# JoystickButtons.net
KiCad netlist of a schematic drawn in Altium Designer
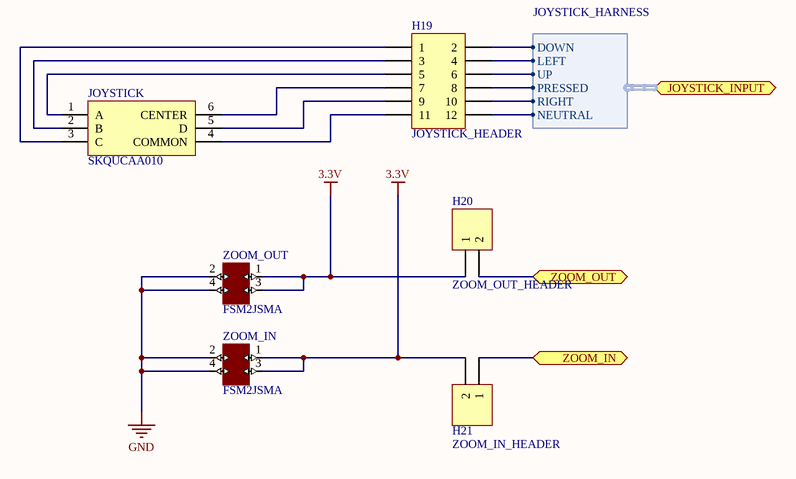
[diagram p0: JoystickButtons.SchDoc]

(export (version "E")
  (design (tool "Eeschema 10.0.6"))
  (components
    (comp (ref "H19")
      (value "JOYSTICK_HEADER")
      (footprint "HDR2X6")
      (description "Header, 6-Pin, Dual row")
      (fields (field (name "PUBLISHER") "Altium Limited"))
      (libsource (lib "Miscellaneous Connectors") (part "Header 6X2"))
    )
    (comp (ref "H20")
      (value "ZOOM_OUT_HEADER")
      (footprint "HDR1X2")
      (description "Header, 2-Pin")
      (fields (field (name "PUBLISHER") "Altium Limited"))
      (libsource (lib "") (part "Header 2_1"))
    )
    (comp (ref "H21")
      (value "ZOOM_IN_HEADER")
      (footprint "HDR1X2")
      (description "Header, 2-Pin")
      (fields (field (name "PUBLISHER") "Altium Limited"))
      (libsource (lib "Miscellaneous Connectors") (part "Header 2"))
    )
    (comp (ref "JOYSTICK")
      (value "SKQUCAA010")
      (footprint "5-WAY-JOYSTICK")
      (libsource (lib "Vector Library") (part "SKQUCAA010"))
    )
    (comp (ref "ZOOM_IN")
      (value "FSM2JSMA")
      (footprint "Button")
      (libsource (lib "Vector Library") (part "switch-button"))
    )
    (comp (ref "ZOOM_OUT")
      (value "FSM2JSMA")
      (footprint "Button")
      (libsource (lib "Vector Library") (part "switch-button"))
    )
  )
  (nets
    (net (code "2") (name "/DOWN") (class "Default")
      (node (ref "H19") (pin "2") (pinfunction "2_2") (pintype "passive"))
    )
    (net (code "3") (name "/LEFT") (class "Default")
      (node (ref "H19") (pin "4") (pinfunction "4_4") (pintype "passive"))
    )
    (net (code "4") (name "/NEUTRAL") (class "Default")
      (node (ref "H19") (pin "12") (pinfunction "12_12") (pintype "passive"))
    )
    (net (code "5") (name "/PRESSED") (class "Default")
      (node (ref "H19") (pin "8") (pinfunction "8_8") (pintype "passive"))
    )
    (net (code "6") (name "/RIGHT") (class "Default")
      (node (ref "H19") (pin "10") (pinfunction "10_10") (pintype "passive"))
    )
    (net (code "7") (name "/UP") (class "Default")
      (node (ref "H19") (pin "6") (pinfunction "6_6") (pintype "passive"))
    )
    (net (code "8") (name "/ZOOM_IN") (class "Default")
      (node (ref "H21") (pin "1") (pinfunction "1_1") (pintype "passive"))
    )
    (net (code "9") (name "/ZOOM_OUT") (class "Default")
      (node (ref "H20") (pin "2") (pinfunction "2_2") (pintype "passive"))
    )
    (net (code "11") (name "3.3V") (class "Default")
      (node (ref "H20") (pin "1") (pinfunction "1_1") (pintype "passive"))
      (node (ref "H21") (pin "2") (pinfunction "2_2") (pintype "passive"))
      (node (ref "ZOOM_IN") (pin "1") (pinfunction "1_1") (pintype "bidirectional"))
      (node (ref "ZOOM_IN") (pin "3") (pinfunction "3_3") (pintype "bidirectional"))
      (node (ref "ZOOM_OUT") (pin "1") (pinfunction "1_1") (pintype "bidirectional"))
      (node (ref "ZOOM_OUT") (pin "3") (pinfunction "3_3") (pintype "bidirectional"))
    )
    (net (code "12") (name "GND") (class "Default")
      (node (ref "ZOOM_IN") (pin "2") (pinfunction "2_2") (pintype "bidirectional"))
      (node (ref "ZOOM_IN") (pin "4") (pinfunction "4_4") (pintype "bidirectional"))
      (node (ref "ZOOM_OUT") (pin "2") (pinfunction "2_2") (pintype "bidirectional"))
      (node (ref "ZOOM_OUT") (pin "4") (pinfunction "4_4") (pintype "bidirectional"))
    )
    (net (code "13") (name "Net-(JOYSTICK-A)") (class "Default")
      (node (ref "H19") (pin "5") (pinfunction "5_5") (pintype "passive"))
      (node (ref "JOYSTICK") (pin "1") (pinfunction "A_1") (pintype "passive"))
    )
    (net (code "14") (name "Net-(JOYSTICK-B)") (class "Default")
      (node (ref "H19") (pin "3") (pinfunction "3_3") (pintype "passive"))
      (node (ref "JOYSTICK") (pin "2") (pinfunction "B_2") (pintype "passive"))
    )
    (net (code "15") (name "Net-(JOYSTICK-C)") (class "Default")
      (node (ref "H19") (pin "1") (pinfunction "1_1") (pintype "passive"))
      (node (ref "JOYSTICK") (pin "3") (pinfunction "C_3") (pintype "passive"))
    )
    (net (code "16") (name "Net-(JOYSTICK-CENTER)") (class "Default")
      (node (ref "H19") (pin "7") (pinfunction "7_7") (pintype "passive"))
      (node (ref "JOYSTICK") (pin "6") (pinfunction "CENTER_6") (pintype "passive"))
    )
    (net (code "17") (name "Net-(JOYSTICK-COMMON)") (class "Default")
      (node (ref "H19") (pin "11") (pinfunction "11_11") (pintype "passive"))
      (node (ref "JOYSTICK") (pin "4") (pinfunction "COMMON_4") (pintype "passive"))
    )
    (net (code "18") (name "Net-(JOYSTICK-D)") (class "Default")
      (node (ref "H19") (pin "9") (pinfunction "9_9") (pintype "passive"))
      (node (ref "JOYSTICK") (pin "5") (pinfunction "D_5") (pintype "passive"))
    )
  )
)
